# binary_watch.net
KiCad netlist of a schematic drawn in EAGLE
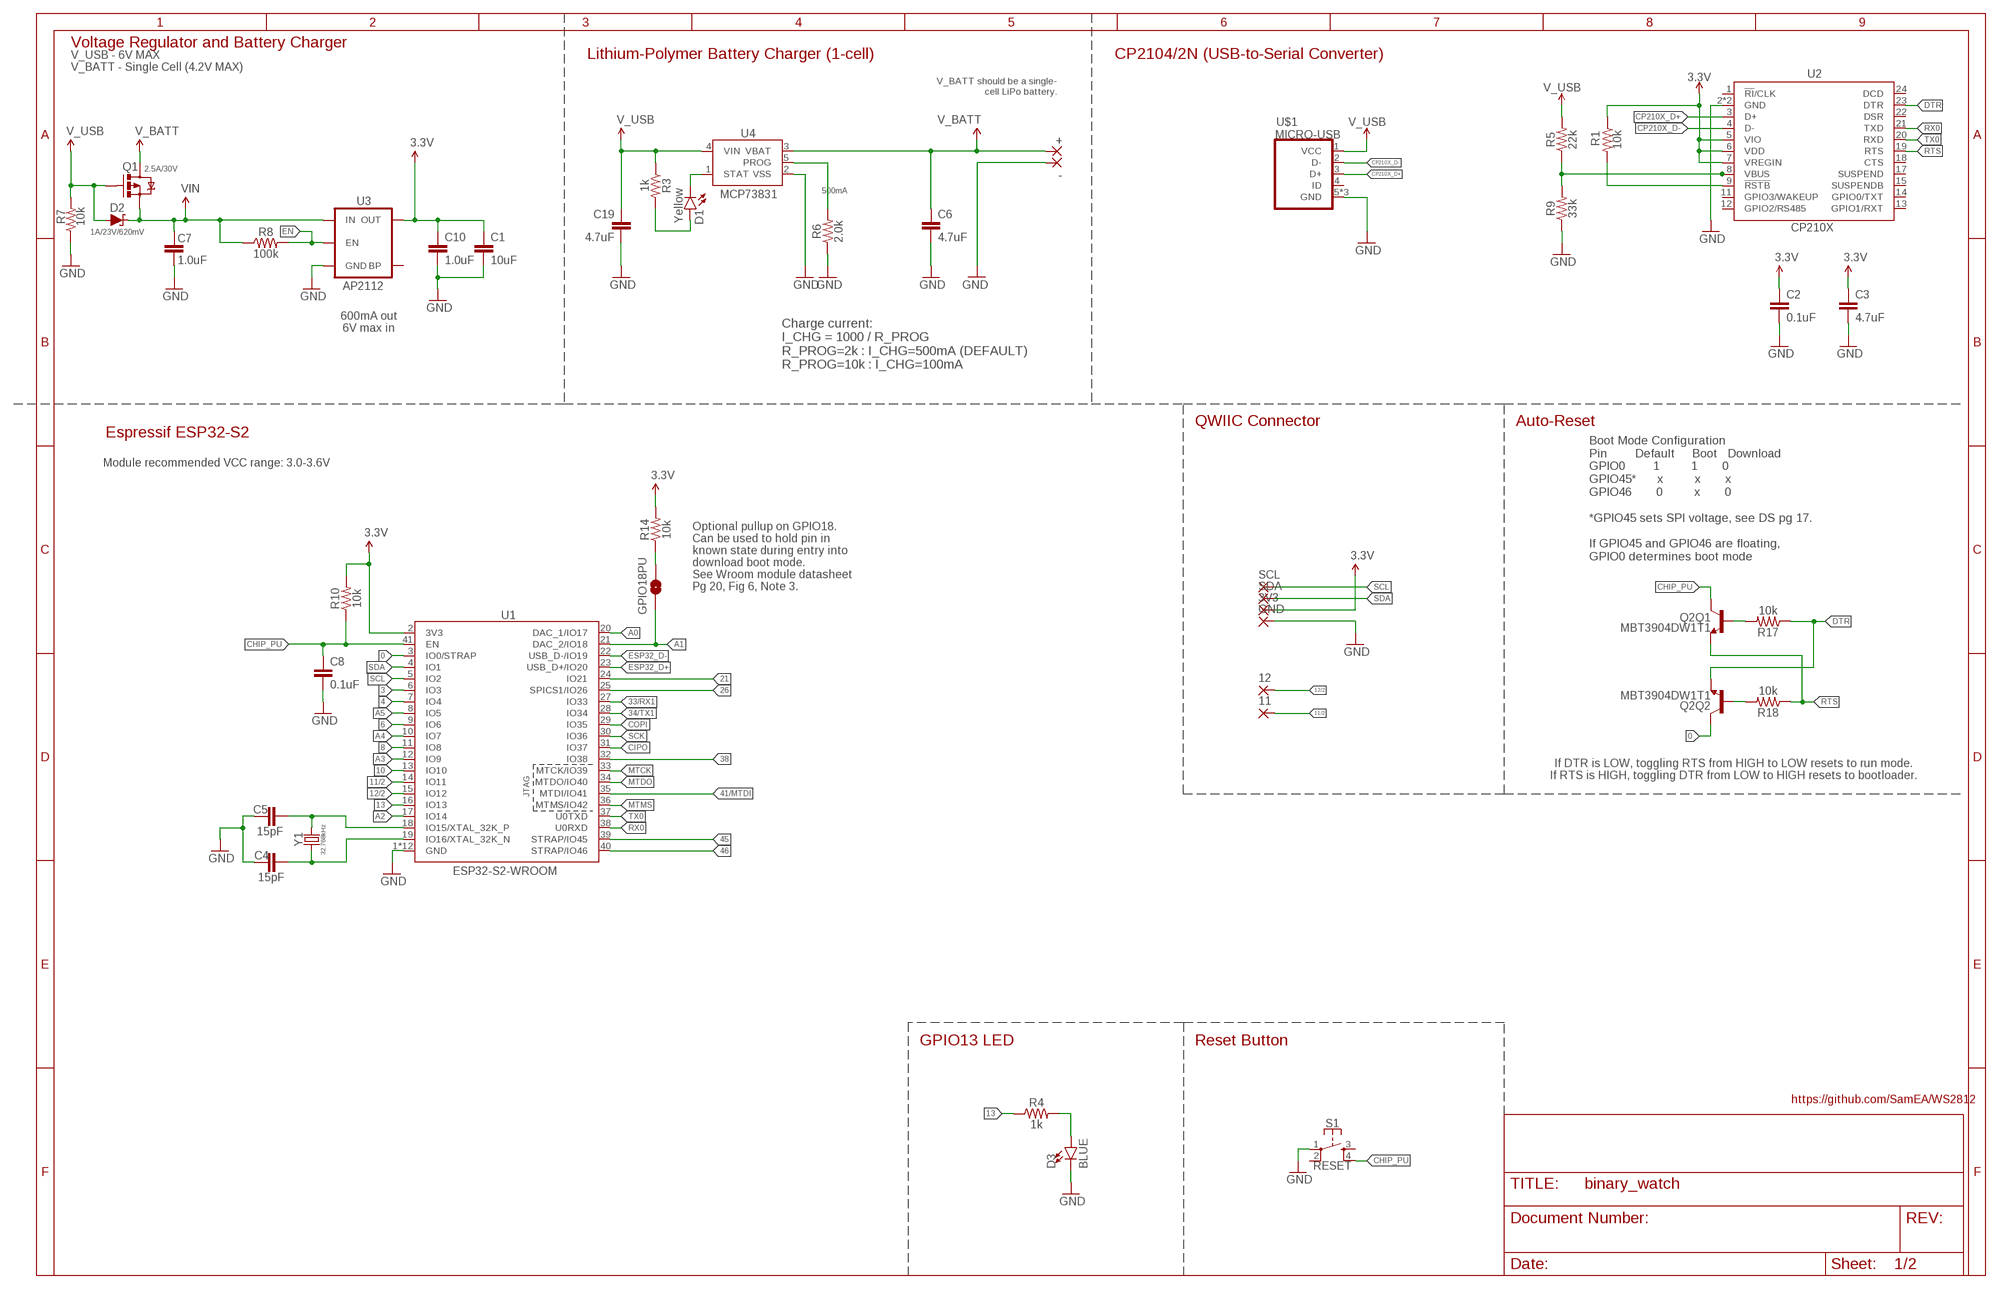
[diagram p0: schematic, sheet 1]
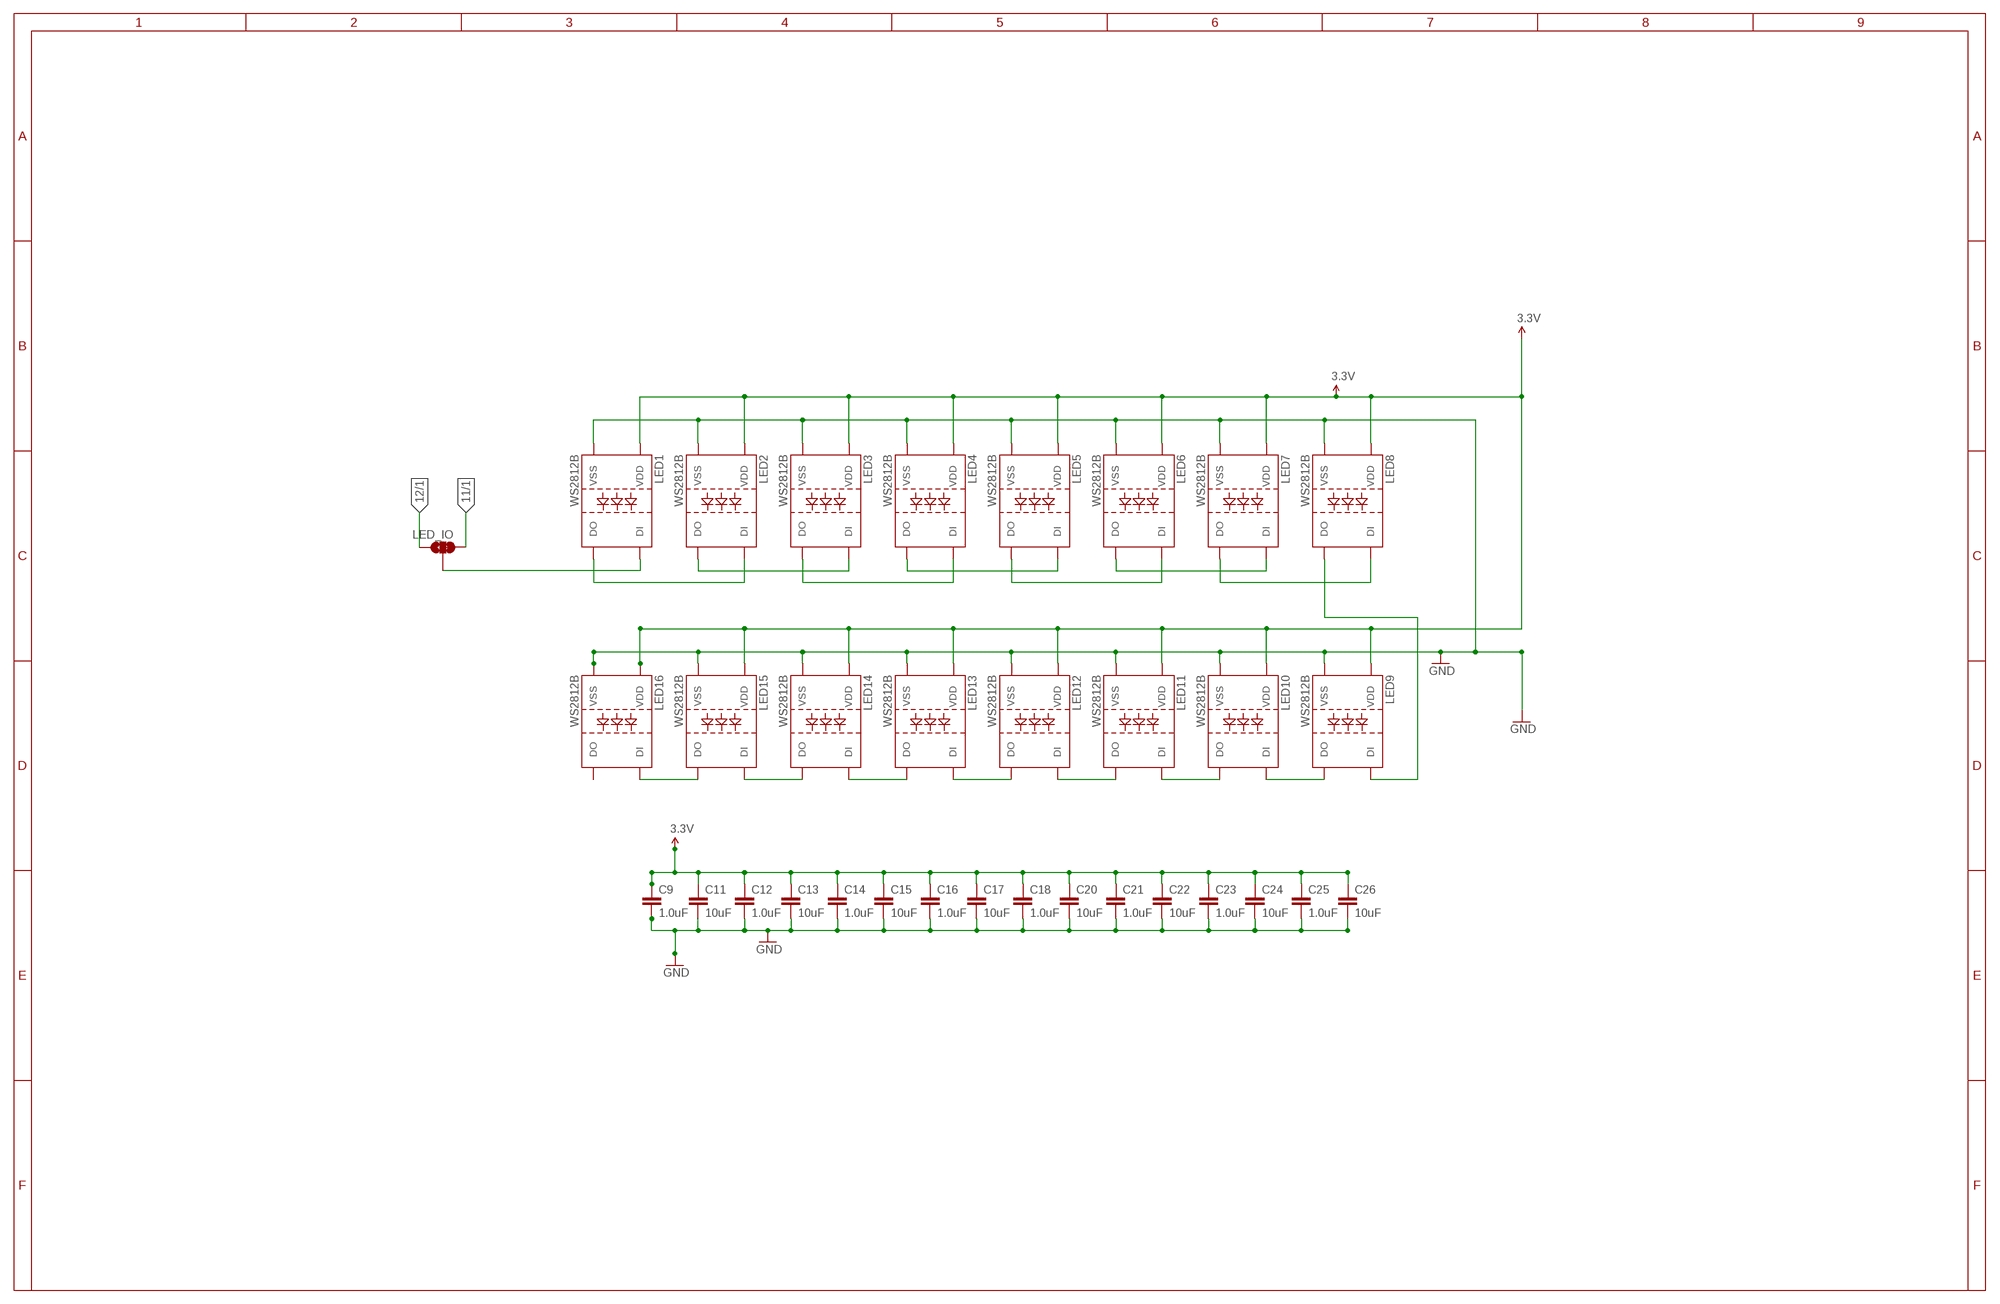
[diagram p1: schematic, sheet 2]

(export (version "E")
  (design (tool "Eeschema 10.0.6"))
  (components
    (comp (ref "C9")
      (value "1.0uF")
      (footprint "eagle-import:0402-TIGHT")
      (libsource (lib "eagle-import") (part "1.0UF-0402T-16V-10%"))
    )
    (comp (ref "C11")
      (value "10uF")
      (footprint "eagle-import:0402-TIGHT")
      (libsource (lib "eagle-import") (part "10UF-0402T-6.3V-20%"))
    )
    (comp (ref "C12")
      (value "1.0uF")
      (footprint "eagle-import:0402-TIGHT")
      (libsource (lib "eagle-import") (part "1.0UF-0402T-16V-10%"))
    )
    (comp (ref "C13")
      (value "10uF")
      (footprint "eagle-import:0402-TIGHT")
      (libsource (lib "eagle-import") (part "10UF-0402T-6.3V-20%"))
    )
    (comp (ref "C14")
      (value "1.0uF")
      (footprint "eagle-import:0402-TIGHT")
      (libsource (lib "eagle-import") (part "1.0UF-0402T-16V-10%"))
    )
    (comp (ref "C15")
      (value "10uF")
      (footprint "eagle-import:0402-TIGHT")
      (libsource (lib "eagle-import") (part "10UF-0402T-6.3V-20%"))
    )
    (comp (ref "C16")
      (value "1.0uF")
      (footprint "eagle-import:0402-TIGHT")
      (libsource (lib "eagle-import") (part "1.0UF-0402T-16V-10%"))
    )
    (comp (ref "C17")
      (value "10uF")
      (footprint "eagle-import:0402-TIGHT")
      (libsource (lib "eagle-import") (part "10UF-0402T-6.3V-20%"))
    )
    (comp (ref "C18")
      (value "1.0uF")
      (footprint "eagle-import:0402-TIGHT")
      (libsource (lib "eagle-import") (part "1.0UF-0402T-16V-10%"))
    )
    (comp (ref "C20")
      (value "10uF")
      (footprint "eagle-import:0402-TIGHT")
      (libsource (lib "eagle-import") (part "10UF-0402T-6.3V-20%"))
    )
    (comp (ref "C21")
      (value "1.0uF")
      (footprint "eagle-import:0402-TIGHT")
      (libsource (lib "eagle-import") (part "1.0UF-0402T-16V-10%"))
    )
    (comp (ref "C22")
      (value "10uF")
      (footprint "eagle-import:0402-TIGHT")
      (libsource (lib "eagle-import") (part "10UF-0402T-6.3V-20%"))
    )
    (comp (ref "C23")
      (value "1.0uF")
      (footprint "eagle-import:0402-TIGHT")
      (libsource (lib "eagle-import") (part "1.0UF-0402T-16V-10%"))
    )
    (comp (ref "C24")
      (value "10uF")
      (footprint "eagle-import:0402-TIGHT")
      (libsource (lib "eagle-import") (part "10UF-0402T-6.3V-20%"))
    )
    (comp (ref "C25")
      (value "1.0uF")
      (footprint "eagle-import:0402-TIGHT")
      (libsource (lib "eagle-import") (part "1.0UF-0402T-16V-10%"))
    )
    (comp (ref "C26")
      (value "10uF")
      (footprint "eagle-import:0402-TIGHT")
      (libsource (lib "eagle-import") (part "10UF-0402T-6.3V-20%"))
    )
    (comp (ref "LED1")
      (value "WS2812B")
      (footprint "eagle-import:WS2812B")
      (libsource (lib "eagle-import") (part "WS2812B"))
    )
    (comp (ref "LED2")
      (value "WS2812B")
      (footprint "eagle-import:WS2812B")
      (libsource (lib "eagle-import") (part "WS2812B"))
    )
    (comp (ref "LED3")
      (value "WS2812B")
      (footprint "eagle-import:WS2812B")
      (libsource (lib "eagle-import") (part "WS2812B"))
    )
    (comp (ref "LED4")
      (value "WS2812B")
      (footprint "eagle-import:WS2812B")
      (libsource (lib "eagle-import") (part "WS2812B"))
    )
    (comp (ref "LED5")
      (value "WS2812B")
      (footprint "eagle-import:WS2812B")
      (libsource (lib "eagle-import") (part "WS2812B"))
    )
    (comp (ref "LED6")
      (value "WS2812B")
      (footprint "eagle-import:WS2812B")
      (libsource (lib "eagle-import") (part "WS2812B"))
    )
    (comp (ref "LED7")
      (value "WS2812B")
      (footprint "eagle-import:WS2812B")
      (libsource (lib "eagle-import") (part "WS2812B"))
    )
    (comp (ref "LED8")
      (value "WS2812B")
      (footprint "eagle-import:WS2812B")
      (libsource (lib "eagle-import") (part "WS2812B"))
    )
    (comp (ref "LED9")
      (value "WS2812B")
      (footprint "eagle-import:WS2812B")
      (libsource (lib "eagle-import") (part "WS2812B"))
    )
    (comp (ref "LED10")
      (value "WS2812B")
      (footprint "eagle-import:WS2812B")
      (libsource (lib "eagle-import") (part "WS2812B"))
    )
    (comp (ref "LED11")
      (value "WS2812B")
      (footprint "eagle-import:WS2812B")
      (libsource (lib "eagle-import") (part "WS2812B"))
    )
    (comp (ref "LED12")
      (value "WS2812B")
      (footprint "eagle-import:WS2812B")
      (libsource (lib "eagle-import") (part "WS2812B"))
    )
    (comp (ref "LED13")
      (value "WS2812B")
      (footprint "eagle-import:WS2812B")
      (libsource (lib "eagle-import") (part "WS2812B"))
    )
    (comp (ref "LED14")
      (value "WS2812B")
      (footprint "eagle-import:WS2812B")
      (libsource (lib "eagle-import") (part "WS2812B"))
    )
    (comp (ref "LED15")
      (value "WS2812B")
      (footprint "eagle-import:WS2812B")
      (libsource (lib "eagle-import") (part "WS2812B"))
    )
    (comp (ref "LED16")
      (value "WS2812B")
      (footprint "eagle-import:WS2812B")
      (libsource (lib "eagle-import") (part "WS2812B"))
    )
    (comp (ref "LED_IO")
      (value "JUMPER-SMT_3_1-NC_TRACE_SILK")
      (footprint "eagle-import:SMT-JUMPER_3_1-NC_TRACE_SILK")
      (libsource (lib "eagle-import") (part "JUMPER-SMT_3_1-NC_TRACE_SILK"))
    )
    (comp (ref "+")
      (value "WIREPAD1,6/0,8")
      (footprint "eagle-import:1,6_0,8")
      (libsource (lib "eagle-import") (part "WIREPAD1,6/0,8"))
    )
    (comp (ref "-")
      (value "WIREPAD1,6/0,8")
      (footprint "eagle-import:1,6_0,8")
      (libsource (lib "eagle-import") (part "WIREPAD1,6/0,8"))
    )
    (comp (ref "3V3")
      (value "1,6/0,8")
      (footprint "eagle-import:1,6_0,8")
      (libsource (lib "eagle-import") (part "1,6/0,8"))
    )
    (comp (ref "11")
      (value "1,6/0,8")
      (footprint "eagle-import:1,6_0,8")
      (libsource (lib "eagle-import") (part "1,6/0,8"))
    )
    (comp (ref "12")
      (value "1,6/0,8")
      (footprint "eagle-import:1,6_0,8")
      (libsource (lib "eagle-import") (part "1,6/0,8"))
    )
    (comp (ref "C1")
      (value "10uF")
      (footprint "eagle-import:0402-TIGHT")
      (libsource (lib "eagle-import") (part "10UF-0402T-6.3V-20%"))
    )
    (comp (ref "C2")
      (value "0.1uF")
      (footprint "eagle-import:0402-TIGHT")
      (libsource (lib "eagle-import") (part "0.1UF-0402T-16V-10%"))
    )
    (comp (ref "C3")
      (value "4.7uF")
      (footprint "eagle-import:0402-TIGHT")
      (libsource (lib "eagle-import") (part "4.7UF-0402_TIGHT-6.3V-20%-X5R"))
    )
    (comp (ref "C4")
      (value "15pF")
      (footprint "eagle-import:0402-TIGHT")
      (libsource (lib "eagle-import") (part "15PF-0402T-50V-5%"))
    )
    (comp (ref "C5")
      (value "15pF")
      (footprint "eagle-import:0402-TIGHT")
      (libsource (lib "eagle-import") (part "15PF-0402T-50V-5%"))
    )
    (comp (ref "C6")
      (value "4.7uF")
      (footprint "eagle-import:0402-TIGHT")
      (libsource (lib "eagle-import") (part "4.7UF-0402_TIGHT-6.3V-20%-X5R"))
    )
    (comp (ref "C7")
      (value "1.0uF")
      (footprint "eagle-import:0402-TIGHT")
      (libsource (lib "eagle-import") (part "1.0UF-0402T-16V-10%"))
    )
    (comp (ref "C8")
      (value "0.1uF")
      (footprint "eagle-import:0402-TIGHT")
      (libsource (lib "eagle-import") (part "0.1UF-0402T-16V-10%"))
    )
    (comp (ref "C10")
      (value "1.0uF")
      (footprint "eagle-import:0402-TIGHT")
      (libsource (lib "eagle-import") (part "1.0UF-0402T-16V-10%"))
    )
    (comp (ref "C19")
      (value "4.7uF")
      (footprint "eagle-import:0402-TIGHT")
      (libsource (lib "eagle-import") (part "4.7UF-0402_TIGHT-6.3V-20%-X5R"))
    )
    (comp (ref "D1")
      (value "Yellow")
      (footprint "eagle-import:LED-0603")
      (libsource (lib "eagle-import") (part "LED-YELLOW0603"))
    )
    (comp (ref "D2")
      (value "1A/23V/620mV")
      (footprint "eagle-import:SOD-323")
      (libsource (lib "eagle-import") (part "DIODE-SCHOTTKY-BAT20J"))
    )
    (comp (ref "D3")
      (value "BLUE")
      (footprint "eagle-import:LED-0603")
      (libsource (lib "eagle-import") (part "LED-BLUE0603"))
    )
    (comp (ref "GND")
      (value "1,6/0,8")
      (footprint "eagle-import:1,6_0,8")
      (libsource (lib "eagle-import") (part "1,6/0,8"))
    )
    (comp (ref "GPIO18PU")
      (value "JUMPER-SMT_2_NO_SILK")
      (footprint "eagle-import:SMT-JUMPER_2_NO_SILK")
      (libsource (lib "eagle-import") (part "JUMPER-SMT_2_NO_SILK"))
    )
    (comp (ref "Q1")
      (value "2.5A/30V")
      (footprint "eagle-import:SOT23-3@1")
      (libsource (lib "eagle-import") (part "MOSFET-PCHANNELDMG2307L"))
    )
    (comp (ref "Q2")
      (value "MBT3904DW1T1")
      (footprint "eagle-import:SC70-6")
      (libsource (lib "eagle-import") (part "TRANS_NPN_DUAL-MBT3904DW1T1"))
    )
    (comp (ref "R1")
      (value "10k")
      (footprint "eagle-import:0402-TIGHT")
      (libsource (lib "eagle-import") (part "10KOHM-0402T-1/16W-1%"))
    )
    (comp (ref "R3")
      (value "1k")
      (footprint "eagle-import:0402-TIGHT")
      (libsource (lib "eagle-import") (part "1KOHM-0402T-1/16W-1%"))
    )
    (comp (ref "R4")
      (value "1k")
      (footprint "eagle-import:0402-TIGHT")
      (libsource (lib "eagle-import") (part "1KOHM-0402T-1/16W-1%"))
    )
    (comp (ref "R5")
      (value "22k")
      (footprint "eagle-import:0402-TIGHT")
      (libsource (lib "eagle-import") (part "22KOHM-0402_TIGHT-1/10W-1%"))
    )
    (comp (ref "R6")
      (value "2.0k")
      (footprint "eagle-import:0603")
      (libsource (lib "eagle-import") (part "2.0KOHM1/10W5%(0603)"))
    )
    (comp (ref "R7")
      (value "10k")
      (footprint "eagle-import:0402-TIGHT")
      (libsource (lib "eagle-import") (part "10KOHM-0402T-1/16W-1%"))
    )
    (comp (ref "R8")
      (value "100k")
      (footprint "eagle-import:0402-TIGHT")
      (libsource (lib "eagle-import") (part "100KOHM-0402T-1/16W-1%"))
    )
    (comp (ref "R9")
      (value "33k")
      (footprint "eagle-import:0402-TIGHT")
      (libsource (lib "eagle-import") (part "33KOHM-0402T-1/16W-1%"))
    )
    (comp (ref "R10")
      (value "10k")
      (footprint "eagle-import:0402-TIGHT")
      (libsource (lib "eagle-import") (part "10KOHM-0402T-1/16W-1%"))
    )
    (comp (ref "R14")
      (value "10k")
      (footprint "eagle-import:0402-TIGHT")
      (libsource (lib "eagle-import") (part "10KOHM-0402T-1/16W-1%"))
    )
    (comp (ref "R17")
      (value "10k")
      (footprint "eagle-import:0402-TIGHT")
      (libsource (lib "eagle-import") (part "10KOHM-0402T-1/16W-1%"))
    )
    (comp (ref "R18")
      (value "10k")
      (footprint "eagle-import:0402-TIGHT")
      (libsource (lib "eagle-import") (part "10KOHM-0402T-1/16W-1%"))
    )
    (comp (ref "S1")
      (value "RESET")
      (footprint "eagle-import:TACTILE_SWITCH_SMD_4.6X2.8MM")
      (libsource (lib "eagle-import") (part "MOMENTARY-SWITCH-SPST-2-SMD-4.6X2.8MM"))
    )
    (comp (ref "SCL")
      (value "1,6/0,8")
      (footprint "eagle-import:1,6_0,8")
      (libsource (lib "eagle-import") (part "1,6/0,8"))
    )
    (comp (ref "SDA")
      (value "1,6/0,8")
      (footprint "eagle-import:1,6_0,8")
      (libsource (lib "eagle-import") (part "1,6/0,8"))
    )
    (comp (ref "U$1")
      (value "MICRO-USB")
      (footprint "eagle-import:MICRO-USB")
      (libsource (lib "eagle-import") (part "MICRO-USB"))
    )
    (comp (ref "U1")
      (value "ESP32-S2-WROOM")
      (footprint "eagle-import:ESP32-S2-WROOM")
      (libsource (lib "eagle-import") (part "ESP32-S2-WROOM"))
    )
    (comp (ref "U2")
      (value "CP210X")
      (footprint "eagle-import:QFN24")
      (libsource (lib "eagle-import") (part "CP2102N"))
    )
    (comp (ref "U3")
      (value "AP2112")
      (footprint "eagle-import:SOT23-5")
      (libsource (lib "eagle-import") (part "V_REG_LDOSMD"))
    )
    (comp (ref "U4")
      (value "MCP73831")
      (footprint "eagle-import:SOT23-5")
      (libsource (lib "eagle-import") (part "MCP73831"))
    )
    (comp (ref "Y1")
      (value "32.768kHz")
      (footprint "eagle-import:CRYSTAL-SMD-3.2X1.5MM")
      (libsource (lib "eagle-import") (part "CRYSTAL-32.768KHZSMD-3.2X1.5"))
    )
  )
  (nets
    (net (code "1") (name "0") (class "Default")
      (node (ref "Q2") (pin "6") (pinfunction "C_6") (pintype "passive"))
      (node (ref "U1") (pin "3") (pinfunction "IO0/STRAP_3") (pintype "bidirectional"))
    )
    (net (code "2") (name "3") (class "Default")
      (node (ref "U1") (pin "6") (pinfunction "IO3_6") (pintype "bidirectional"))
    )
    (net (code "3") (name "3.3V") (class "Default")
      (node (ref "3V3") (pin "1") (pinfunction "P_1") (pintype "passive"))
      (node (ref "C1") (pin "1") (pinfunction "1_1") (pintype "passive"))
      (node (ref "C10") (pin "1") (pinfunction "1_1") (pintype "passive"))
      (node (ref "C11") (pin "1") (pinfunction "1_1") (pintype "passive"))
      (node (ref "C12") (pin "1") (pinfunction "1_1") (pintype "passive"))
      (node (ref "C13") (pin "1") (pinfunction "1_1") (pintype "passive"))
      (node (ref "C14") (pin "1") (pinfunction "1_1") (pintype "passive"))
      (node (ref "C15") (pin "1") (pinfunction "1_1") (pintype "passive"))
      (node (ref "C16") (pin "1") (pinfunction "1_1") (pintype "passive"))
      (node (ref "C17") (pin "1") (pinfunction "1_1") (pintype "passive"))
      (node (ref "C18") (pin "1") (pinfunction "1_1") (pintype "passive"))
      (node (ref "C2") (pin "1") (pinfunction "1_1") (pintype "passive"))
      (node (ref "C20") (pin "1") (pinfunction "1_1") (pintype "passive"))
      (node (ref "C21") (pin "1") (pinfunction "1_1") (pintype "passive"))
      (node (ref "C22") (pin "1") (pinfunction "1_1") (pintype "passive"))
      (node (ref "C23") (pin "1") (pinfunction "1_1") (pintype "passive"))
      (node (ref "C24") (pin "1") (pinfunction "1_1") (pintype "passive"))
      (node (ref "C25") (pin "1") (pinfunction "1_1") (pintype "passive"))
      (node (ref "C26") (pin "1") (pinfunction "1_1") (pintype "passive"))
      (node (ref "C3") (pin "1") (pinfunction "1_1") (pintype "passive"))
      (node (ref "C9") (pin "1") (pinfunction "1_1") (pintype "passive"))
      (node (ref "LED1") (pin "1") (pinfunction "VDD_1") (pintype "bidirectional"))
      (node (ref "LED10") (pin "1") (pinfunction "VDD_1") (pintype "bidirectional"))
      (node (ref "LED11") (pin "1") (pinfunction "VDD_1") (pintype "bidirectional"))
      (node (ref "LED12") (pin "1") (pinfunction "VDD_1") (pintype "bidirectional"))
      (node (ref "LED13") (pin "1") (pinfunction "VDD_1") (pintype "bidirectional"))
      (node (ref "LED14") (pin "1") (pinfunction "VDD_1") (pintype "bidirectional"))
      (node (ref "LED15") (pin "1") (pinfunction "VDD_1") (pintype "bidirectional"))
      (node (ref "LED16") (pin "1") (pinfunction "VDD_1") (pintype "bidirectional"))
      (node (ref "LED2") (pin "1") (pinfunction "VDD_1") (pintype "bidirectional"))
      (node (ref "LED3") (pin "1") (pinfunction "VDD_1") (pintype "bidirectional"))
      (node (ref "LED4") (pin "1") (pinfunction "VDD_1") (pintype "bidirectional"))
      (node (ref "LED5") (pin "1") (pinfunction "VDD_1") (pintype "bidirectional"))
      (node (ref "LED6") (pin "1") (pinfunction "VDD_1") (pintype "bidirectional"))
      (node (ref "LED7") (pin "1") (pinfunction "VDD_1") (pintype "bidirectional"))
      (node (ref "LED8") (pin "1") (pinfunction "VDD_1") (pintype "bidirectional"))
      (node (ref "LED9") (pin "1") (pinfunction "VDD_1") (pintype "bidirectional"))
      (node (ref "R1") (pin "1") (pinfunction "1_1") (pintype "passive"))
      (node (ref "R10") (pin "2") (pinfunction "2_2") (pintype "passive"))
      (node (ref "R14") (pin "2") (pinfunction "2_2") (pintype "passive"))
      (node (ref "U1") (pin "2") (pinfunction "3V3_2") (pintype "bidirectional"))
      (node (ref "U2") (pin "5") (pinfunction "VIO_5") (pintype "bidirectional"))
      (node (ref "U2") (pin "6") (pinfunction "VDD_6") (pintype "bidirectional"))
      (node (ref "U2") (pin "7") (pinfunction "VREGIN_7") (pintype "bidirectional"))
      (node (ref "U3") (pin "5") (pinfunction "OUT_5") (pintype "passive"))
    )
    (net (code "4") (name "4") (class "Default")
      (node (ref "U1") (pin "7") (pinfunction "IO4_7") (pintype "bidirectional"))
    )
    (net (code "5") (name "6") (class "Default")
      (node (ref "U1") (pin "9") (pinfunction "IO6_9") (pintype "bidirectional"))
    )
    (net (code "6") (name "8") (class "Default")
      (node (ref "U1") (pin "11") (pinfunction "IO8_11") (pintype "bidirectional"))
    )
    (net (code "7") (name "10") (class "Default")
      (node (ref "U1") (pin "13") (pinfunction "IO10_13") (pintype "bidirectional"))
    )
    (net (code "8") (name "11") (class "Default")
      (node (ref "11") (pin "1") (pinfunction "P_1") (pintype "passive"))
      (node (ref "LED_IO") (pin "3") (pinfunction "3_3") (pintype "passive"))
      (node (ref "U1") (pin "14") (pinfunction "IO11_14") (pintype "bidirectional"))
    )
    (net (code "9") (name "12") (class "Default")
      (node (ref "12") (pin "1") (pinfunction "P_1") (pintype "passive"))
      (node (ref "LED_IO") (pin "1") (pinfunction "1_1") (pintype "passive"))
      (node (ref "U1") (pin "15") (pinfunction "IO12_15") (pintype "bidirectional"))
    )
    (net (code "10") (name "13") (class "Default")
      (node (ref "R4") (pin "1") (pinfunction "1_1") (pintype "passive"))
      (node (ref "U1") (pin "16") (pinfunction "IO13_16") (pintype "bidirectional"))
    )
    (net (code "11") (name "21") (class "Default")
      (node (ref "U1") (pin "24") (pinfunction "IO21_24") (pintype "bidirectional"))
    )
    (net (code "12") (name "26") (class "Default")
      (node (ref "U1") (pin "25") (pinfunction "SPICS1/IO26_25") (pintype "bidirectional"))
    )
    (net (code "13") (name "33{slash}RX1") (class "Default")
      (node (ref "U1") (pin "27") (pinfunction "IO33_27") (pintype "bidirectional"))
    )
    (net (code "14") (name "34{slash}TX1") (class "Default")
      (node (ref "U1") (pin "28") (pinfunction "IO34_28") (pintype "bidirectional"))
    )
    (net (code "15") (name "38") (class "Default")
      (node (ref "U1") (pin "32") (pinfunction "IO38_32") (pintype "bidirectional"))
    )
    (net (code "16") (name "41{slash}MTDI") (class "Default")
      (node (ref "U1") (pin "35") (pinfunction "MTDI/IO41_35") (pintype "bidirectional"))
    )
    (net (code "17") (name "45") (class "Default")
      (node (ref "U1") (pin "39") (pinfunction "STRAP/IO45_39") (pintype "bidirectional"))
    )
    (net (code "18") (name "46") (class "Default")
      (node (ref "U1") (pin "40") (pinfunction "STRAP/IO46_40") (pintype "bidirectional"))
    )
    (net (code "19") (name "A0") (class "Default")
      (node (ref "U1") (pin "20") (pinfunction "DAC_1/IO17_20") (pintype "bidirectional"))
    )
    (net (code "20") (name "A1") (class "Default")
      (node (ref "GPIO18PU") (pin "1") (pinfunction "1_1") (pintype "passive"))
      (node (ref "U1") (pin "21") (pinfunction "DAC_2/IO18_21") (pintype "bidirectional"))
    )
    (net (code "21") (name "A2") (class "Default")
      (node (ref "U1") (pin "17") (pinfunction "IO14_17") (pintype "bidirectional"))
    )
    (net (code "22") (name "A3") (class "Default")
      (node (ref "U1") (pin "12") (pinfunction "IO9_12") (pintype "bidirectional"))
    )
    (net (code "23") (name "A4") (class "Default")
      (node (ref "U1") (pin "10") (pinfunction "IO7_10") (pintype "bidirectional"))
    )
    (net (code "24") (name "A5") (class "Default")
      (node (ref "U1") (pin "8") (pinfunction "IO5_8") (pintype "bidirectional"))
    )
    (net (code "25") (name "CHIP_PU") (class "Default")
      (node (ref "C8") (pin "1") (pinfunction "1_1") (pintype "passive"))
      (node (ref "Q2") (pin "3") (pinfunction "C_3") (pintype "passive"))
      (node (ref "R10") (pin "1") (pinfunction "1_1") (pintype "passive"))
      (node (ref "S1") (pin "4") (pinfunction "4_4") (pintype "passive"))
      (node (ref "U1") (pin "41") (pinfunction "EN_41") (pintype "bidirectional"))
    )
    (net (code "26") (name "CIPO") (class "Default")
      (node (ref "U1") (pin "31") (pinfunction "IO37_31") (pintype "bidirectional"))
    )
    (net (code "27") (name "COPI") (class "Default")
      (node (ref "U1") (pin "29") (pinfunction "IO35_29") (pintype "bidirectional"))
    )
    (net (code "28") (name "CP210X_D+") (class "Default")
      (node (ref "U$1") (pin "3") (pinfunction "D+_3") (pintype "bidirectional"))
      (node (ref "U2") (pin "3") (pinfunction "D+_3") (pintype "bidirectional"))
    )
    (net (code "29") (name "CP210X_D-") (class "Default")
      (node (ref "U$1") (pin "2") (pinfunction "D-_2") (pintype "bidirectional"))
      (node (ref "U2") (pin "4") (pinfunction "D-_4") (pintype "bidirectional"))
    )
    (net (code "30") (name "DTR") (class "Default")
      (node (ref "Q2") (pin "1") (pinfunction "E_1") (pintype "passive"))
      (node (ref "R17") (pin "1") (pinfunction "1_1") (pintype "passive"))
      (node (ref "U2") (pin "23") (pinfunction "DTR_23") (pintype "bidirectional"))
    )
    (net (code "31") (name "EN") (class "Default")
      (node (ref "R8") (pin "2") (pinfunction "2_2") (pintype "passive"))
      (node (ref "U3") (pin "3") (pinfunction "EN_3") (pintype "input"))
    )
    (net (code "32") (name "ESP32_D+") (class "Default")
      (node (ref "U1") (pin "23") (pinfunction "USB_D+/IO20_23") (pintype "bidirectional"))
    )
    (net (code "33") (name "ESP32_D-") (class "Default")
      (node (ref "U1") (pin "22") (pinfunction "USB_D-/IO19_22") (pintype "bidirectional"))
    )
    (net (code "34") (name "GND") (class "Default")
      (node (ref "-") (pin "1") (pinfunction "P_1") (pintype "passive"))
      (node (ref "C1") (pin "2") (pinfunction "2_2") (pintype "passive"))
      (node (ref "C10") (pin "2") (pinfunction "2_2") (pintype "passive"))
      (node (ref "C11") (pin "2") (pinfunction "2_2") (pintype "passive"))
      (node (ref "C12") (pin "2") (pinfunction "2_2") (pintype "passive"))
      (node (ref "C13") (pin "2") (pinfunction "2_2") (pintype "passive"))
      (node (ref "C14") (pin "2") (pinfunction "2_2") (pintype "passive"))
      (node (ref "C15") (pin "2") (pinfunction "2_2") (pintype "passive"))
      (node (ref "C16") (pin "2") (pinfunction "2_2") (pintype "passive"))
      (node (ref "C17") (pin "2") (pinfunction "2_2") (pintype "passive"))
      (node (ref "C18") (pin "2") (pinfunction "2_2") (pintype "passive"))
      (node (ref "C19") (pin "2") (pinfunction "2_2") (pintype "passive"))
      (node (ref "C2") (pin "2") (pinfunction "2_2") (pintype "passive"))
      (node (ref "C20") (pin "2") (pinfunction "2_2") (pintype "passive"))
      (node (ref "C21") (pin "2") (pinfunction "2_2") (pintype "passive"))
      (node (ref "C22") (pin "2") (pinfunction "2_2") (pintype "passive"))
      (node (ref "C23") (pin "2") (pinfunction "2_2") (pintype "passive"))
      (node (ref "C24") (pin "2") (pinfunction "2_2") (pintype "passive"))
      (node (ref "C25") (pin "2") (pinfunction "2_2") (pintype "passive"))
      (node (ref "C26") (pin "2") (pinfunction "2_2") (pintype "passive"))
      (node (ref "C3") (pin "2") (pinfunction "2_2") (pintype "passive"))
      (node (ref "C4") (pin "1") (pinfunction "1_1") (pintype "passive"))
      (node (ref "C5") (pin "1") (pinfunction "1_1") (pintype "passive"))
      (node (ref "C6") (pin "2") (pinfunction "2_2") (pintype "passive"))
      (node (ref "C7") (pin "2") (pinfunction "2_2") (pintype "passive"))
      (node (ref "C8") (pin "2") (pinfunction "2_2") (pintype "passive"))
      (node (ref "C9") (pin "2") (pinfunction "2_2") (pintype "passive"))
      (node (ref "D3") (pin "C") (pinfunction "C_C") (pintype "passive"))
      (node (ref "GND") (pin "1") (pinfunction "P_1") (pintype "passive"))
      (node (ref "LED1") (pin "3") (pinfunction "VSS_3") (pintype "bidirectional"))
      (node (ref "LED10") (pin "3") (pinfunction "VSS_3") (pintype "bidirectional"))
      (node (ref "LED11") (pin "3") (pinfunction "VSS_3") (pintype "bidirectional"))
      (node (ref "LED12") (pin "3") (pinfunction "VSS_3") (pintype "bidirectional"))
      (node (ref "LED13") (pin "3") (pinfunction "VSS_3") (pintype "bidirectional"))
      (node (ref "LED14") (pin "3") (pinfunction "VSS_3") (pintype "bidirectional"))
      (node (ref "LED15") (pin "3") (pinfunction "VSS_3") (pintype "bidirectional"))
      (node (ref "LED16") (pin "3") (pinfunction "VSS_3") (pintype "bidirectional"))
      (node (ref "LED2") (pin "3") (pinfunction "VSS_3") (pintype "bidirectional"))
      (node (ref "LED3") (pin "3") (pinfunction "VSS_3") (pintype "bidirectional"))
      (node (ref "LED4") (pin "3") (pinfunction "VSS_3") (pintype "bidirectional"))
      (node (ref "LED5") (pin "3") (pinfunction "VSS_3") (pintype "bidirectional"))
      (node (ref "LED6") (pin "3") (pinfunction "VSS_3") (pintype "bidirectional"))
      (node (ref "LED7") (pin "3") (pinfunction "VSS_3") (pintype "bidirectional"))
      (node (ref "LED8") (pin "3") (pinfunction "VSS_3") (pintype "bidirectional"))
      (node (ref "LED9") (pin "3") (pinfunction "VSS_3") (pintype "bidirectional"))
      (node (ref "R6") (pin "1") (pinfunction "1_1") (pintype "passive"))
      (node (ref "R7") (pin "1") (pinfunction "1_1") (pintype "passive"))
      (node (ref "R9") (pin "1") (pinfunction "1_1") (pintype "passive"))
      (node (ref "S1") (pin "1") (pinfunction "1_1") (pintype "passive"))
      (node (ref "U$1") (pin "5") (pinfunction "GND_5") (pintype "power_in"))
      (node (ref "U$1") (pin "GND1") (pinfunction "GND_GND1") (pintype "power_in"))
      (node (ref "U$1") (pin "GND2") (pinfunction "GND_GND2") (pintype "power_in"))
      (node (ref "U1") (pin "1") (pinfunction "GND_1") (pintype "bidirectional"))
      (node (ref "U1") (pin "26") (pinfunction "GND_26") (pintype "bidirectional"))
      (node (ref "U1") (pin "42") (pinfunction "GND_42") (pintype "bidirectional"))
      (node (ref "U1") (pin "GNDEP0") (pinfunction "GND_GNDEP0") (pintype "bidirectional"))
      (node (ref "U1") (pin "GNDEP1") (pinfunction "GND_GNDEP1") (pintype "bidirectional"))
      (node (ref "U1") (pin "GNDEP2") (pinfunction "GND_GNDEP2") (pintype "bidirectional"))
      (node (ref "U1") (pin "GNDEP3") (pinfunction "GND_GNDEP3") (pintype "bidirectional"))
      (node (ref "U1") (pin "GNDEP4") (pinfunction "GND_GNDEP4") (pintype "bidirectional"))
      (node (ref "U1") (pin "GNDEP5") (pinfunction "GND_GNDEP5") (pintype "bidirectional"))
      (node (ref "U1") (pin "GNDEP6") (pinfunction "GND_GNDEP6") (pintype "bidirectional"))
      (node (ref "U1") (pin "GNDEP7") (pinfunction "GND_GNDEP7") (pintype "bidirectional"))
      (node (ref "U1") (pin "GNDEP8") (pinfunction "GND_GNDEP8") (pintype "bidirectional"))
      (node (ref "U2") (pin "2") (pinfunction "GND_2") (pintype "bidirectional"))
      (node (ref "U2") (pin "PAD") (pinfunction "GND_PAD") (pintype "bidirectional"))
      (node (ref "U3") (pin "2") (pinfunction "GND_2") (pintype "input"))
      (node (ref "U4") (pin "2") (pinfunction "VSS_2") (pintype "power_in"))
    )
    (net (code "35") (name "MTCK") (class "Default")
      (node (ref "U1") (pin "33") (pinfunction "MTCK/IO39_33") (pintype "bidirectional"))
    )
    (net (code "36") (name "MTDO") (class "Default")
      (node (ref "U1") (pin "34") (pinfunction "MTDO/IO40_34") (pintype "bidirectional"))
    )
    (net (code "37") (name "MTMS") (class "Default")
      (node (ref "U1") (pin "36") (pinfunction "MTMS/IO42_36") (pintype "bidirectional"))
    )
    (net (code "38") (name "Net-(D1-PadA)") (class "Default")
      (node (ref "D1") (pin "A") (pinfunction "A_A") (pintype "passive"))
      (node (ref "R3") (pin "2") (pinfunction "2_2") (pintype "passive"))
    )
    (net (code "39") (name "Net-(D3-PadA)") (class "Default")
      (node (ref "D3") (pin "A") (pinfunction "A_A") (pintype "passive"))
      (node (ref "R4") (pin "2") (pinfunction "2_2") (pintype "passive"))
    )
    (net (code "40") (name "Net-(GPIO18PU-Pad2)") (class "Default")
      (node (ref "GPIO18PU") (pin "2") (pinfunction "2_2") (pintype "passive"))
      (node (ref "R14") (pin "1") (pinfunction "1_1") (pintype "passive"))
    )
    (net (code "41") (name "Net-(LED1-DI)") (class "Default")
      (node (ref "LED1") (pin "4") (pinfunction "DI_4") (pintype "bidirectional"))
      (node (ref "LED_IO") (pin "2") (pinfunction "2_2") (pintype "passive"))
    )
    (net (code "42") (name "Net-(LED1-DO)") (class "Default")
      (node (ref "LED1") (pin "2") (pinfunction "DO_2") (pintype "bidirectional"))
      (node (ref "LED2") (pin "4") (pinfunction "DI_4") (pintype "bidirectional"))
    )
    (net (code "43") (name "Net-(LED2-DO)") (class "Default")
      (node (ref "LED2") (pin "2") (pinfunction "DO_2") (pintype "bidirectional"))
      (node (ref "LED3") (pin "4") (pinfunction "DI_4") (pintype "bidirectional"))
    )
    (net (code "44") (name "Net-(LED3-DO)") (class "Default")
      (node (ref "LED3") (pin "2") (pinfunction "DO_2") (pintype "bidirectional"))
      (node (ref "LED4") (pin "4") (pinfunction "DI_4") (pintype "bidirectional"))
    )
    (net (code "45") (name "Net-(LED4-DO)") (class "Default")
      (node (ref "LED4") (pin "2") (pinfunction "DO_2") (pintype "bidirectional"))
      (node (ref "LED5") (pin "4") (pinfunction "DI_4") (pintype "bidirectional"))
    )
    (net (code "46") (name "Net-(LED5-DO)") (class "Default")
      (node (ref "LED5") (pin "2") (pinfunction "DO_2") (pintype "bidirectional"))
      (node (ref "LED6") (pin "4") (pinfunction "DI_4") (pintype "bidirectional"))
    )
    (net (code "47") (name "Net-(LED6-DO)") (class "Default")
      (node (ref "LED6") (pin "2") (pinfunction "DO_2") (pintype "bidirectional"))
      (node (ref "LED7") (pin "4") (pinfunction "DI_4") (pintype "bidirectional"))
    )
    (net (code "48") (name "Net-(LED7-DO)") (class "Default")
      (node (ref "LED7") (pin "2") (pinfunction "DO_2") (pintype "bidirectional"))
      (node (ref "LED8") (pin "4") (pinfunction "DI_4") (pintype "bidirectional"))
    )
    (net (code "49") (name "Net-(LED8-DO)") (class "Default")
      (node (ref "LED8") (pin "2") (pinfunction "DO_2") (pintype "bidirectional"))
      (node (ref "LED9") (pin "4") (pinfunction "DI_4") (pintype "bidirectional"))
    )
    (net (code "50") (name "Net-(LED10-DI)") (class "Default")
      (node (ref "LED10") (pin "4") (pinfunction "DI_4") (pintype "bidirectional"))
      (node (ref "LED9") (pin "2") (pinfunction "DO_2") (pintype "bidirectional"))
    )
    (net (code "51") (name "Net-(LED10-DO)") (class "Default")
      (node (ref "LED10") (pin "2") (pinfunction "DO_2") (pintype "bidirectional"))
      (node (ref "LED11") (pin "4") (pinfunction "DI_4") (pintype "bidirectional"))
    )
    (net (code "52") (name "Net-(LED11-DO)") (class "Default")
      (node (ref "LED11") (pin "2") (pinfunction "DO_2") (pintype "bidirectional"))
      (node (ref "LED12") (pin "4") (pinfunction "DI_4") (pintype "bidirectional"))
    )
    (net (code "53") (name "Net-(LED12-DO)") (class "Default")
      (node (ref "LED12") (pin "2") (pinfunction "DO_2") (pintype "bidirectional"))
      (node (ref "LED13") (pin "4") (pinfunction "DI_4") (pintype "bidirectional"))
    )
    (net (code "54") (name "Net-(LED13-DO)") (class "Default")
      (node (ref "LED13") (pin "2") (pinfunction "DO_2") (pintype "bidirectional"))
      (node (ref "LED14") (pin "4") (pinfunction "DI_4") (pintype "bidirectional"))
    )
    (net (code "55") (name "Net-(LED14-DO)") (class "Default")
      (node (ref "LED14") (pin "2") (pinfunction "DO_2") (pintype "bidirectional"))
      (node (ref "LED15") (pin "4") (pinfunction "DI_4") (pintype "bidirectional"))
    )
    (net (code "56") (name "Net-(LED15-DO)") (class "Default")
      (node (ref "LED15") (pin "2") (pinfunction "DO_2") (pintype "bidirectional"))
      (node (ref "LED16") (pin "4") (pinfunction "DI_4") (pintype "bidirectional"))
    )
    (net (code "57") (name "Net-(Q2A-B)") (class "Default")
      (node (ref "Q2") (pin "5") (pinfunction "B_5") (pintype "passive"))
      (node (ref "R17") (pin "2") (pinfunction "2_2") (pintype "passive"))
    )
    (net (code "58") (name "Net-(Q2B-B)") (class "Default")
      (node (ref "Q2") (pin "2") (pinfunction "B_2") (pintype "passive"))
      (node (ref "R18") (pin "2") (pinfunction "2_2") (pintype "passive"))
    )
    (net (code "59") (name "Net-(U1-IO15{slash}XTAL_32K_P)") (class "Default")
      (node (ref "C5") (pin "2") (pinfunction "2_2") (pintype "passive"))
      (node (ref "U1") (pin "18") (pinfunction "IO15/XTAL_32K_P_18") (pintype "bidirectional"))
      (node (ref "Y1") (pin "P$2") (pinfunction "2_P$2") (pintype "passive"))
    )
    (net (code "60") (name "Net-(U1-IO16{slash}XTAL_32K_N)") (class "Default")
      (node (ref "C4") (pin "2") (pinfunction "2_2") (pintype "passive"))
      (node (ref "U1") (pin "19") (pinfunction "IO16/XTAL_32K_N_19") (pintype "bidirectional"))
      (node (ref "Y1") (pin "P$1") (pinfunction "1_P$1") (pintype "passive"))
    )
    (net (code "61") (name "Net-(U2-VBUS)") (class "Default")
      (node (ref "R5") (pin "1") (pinfunction "1_1") (pintype "passive"))
      (node (ref "R9") (pin "2") (pinfunction "2_2") (pintype "passive"))
      (node (ref "U2") (pin "8") (pinfunction "VBUS_8") (pintype "bidirectional"))
    )
    (net (code "62") (name "Net-(U2-~{RSTB})") (class "Default")
      (node (ref "R1") (pin "2") (pinfunction "2_2") (pintype "passive"))
      (node (ref "U2") (pin "9") (pinfunction "~{RSTB}_9") (pintype "bidirectional"))
    )
    (net (code "63") (name "Net-(U4-PROG)") (class "Default")
      (node (ref "R6") (pin "2") (pinfunction "2_2") (pintype "passive"))
      (node (ref "U4") (pin "5") (pinfunction "PROG_5") (pintype "input"))
    )
    (net (code "64") (name "Net-(U4-STAT)") (class "Default")
      (node (ref "D1") (pin "C") (pinfunction "C_C") (pintype "passive"))
      (node (ref "U4") (pin "1") (pinfunction "STAT_1") (pintype "output"))
    )
    (net (code "65") (name "RTS") (class "Default")
      (node (ref "Q2") (pin "4") (pinfunction "E_4") (pintype "passive"))
      (node (ref "R18") (pin "1") (pinfunction "1_1") (pintype "passive"))
      (node (ref "U2") (pin "19") (pinfunction "RTS_19") (pintype "bidirectional"))
    )
    (net (code "66") (name "RX0") (class "Default")
      (node (ref "U1") (pin "38") (pinfunction "U0RXD_38") (pintype "bidirectional"))
      (node (ref "U2") (pin "21") (pinfunction "TXD_21") (pintype "bidirectional"))
    )
    (net (code "67") (name "SCK") (class "Default")
      (node (ref "U1") (pin "30") (pinfunction "IO36_30") (pintype "bidirectional"))
    )
    (net (code "68") (name "SCL") (class "Default")
      (node (ref "SCL") (pin "1") (pinfunction "P_1") (pintype "passive"))
      (node (ref "U1") (pin "5") (pinfunction "IO2_5") (pintype "bidirectional"))
    )
    (net (code "69") (name "SDA") (class "Default")
      (node (ref "SDA") (pin "1") (pinfunction "P_1") (pintype "passive"))
      (node (ref "U1") (pin "4") (pinfunction "IO1_4") (pintype "bidirectional"))
    )
    (net (code "70") (name "TX0") (class "Default")
      (node (ref "U1") (pin "37") (pinfunction "U0TXD_37") (pintype "bidirectional"))
      (node (ref "U2") (pin "20") (pinfunction "RXD_20") (pintype "bidirectional"))
    )
    (net (code "71") (name "VIN") (class "Default")
      (node (ref "C7") (pin "1") (pinfunction "1_1") (pintype "passive"))
      (node (ref "D2") (pin "C") (pinfunction "C_C") (pintype "passive"))
      (node (ref "Q1") (pin "2") (pinfunction "S_2") (pintype "passive"))
      (node (ref "R8") (pin "1") (pinfunction "1_1") (pintype "passive"))
      (node (ref "U3") (pin "1") (pinfunction "IN_1") (pintype "input"))
    )
    (net (code "72") (name "V_BATT") (class "Default")
      (node (ref "+") (pin "1") (pinfunction "P_1") (pintype "passive"))
      (node (ref "C6") (pin "1") (pinfunction "1_1") (pintype "passive"))
      (node (ref "Q1") (pin "3") (pinfunction "D_3") (pintype "passive"))
      (node (ref "U4") (pin "3") (pinfunction "VBAT_3") (pintype "power_in"))
    )
    (net (code "73") (name "V_USB") (class "Default")
      (node (ref "C19") (pin "1") (pinfunction "1_1") (pintype "passive"))
      (node (ref "D2") (pin "A") (pinfunction "A_A") (pintype "passive"))
      (node (ref "Q1") (pin "1") (pinfunction "G_1") (pintype "passive"))
      (node (ref "R3") (pin "1") (pinfunction "1_1") (pintype "passive"))
      (node (ref "R5") (pin "2") (pinfunction "2_2") (pintype "passive"))
      (node (ref "R7") (pin "2") (pinfunction "2_2") (pintype "passive"))
      (node (ref "U$1") (pin "1") (pinfunction "VCC_1") (pintype "power_in"))
      (node (ref "U4") (pin "4") (pinfunction "VIN_4") (pintype "power_in"))
    )
    (net (code "74") (name "unconnected-(LED16-DO-Pad2)") (class "Default")
      (node (ref "LED16") (pin "2") (pinfunction "DO_2") (pintype "bidirectional"))
    )
    (net (code "75") (name "unconnected-(S1-Pad2)") (class "Default")
      (node (ref "S1") (pin "2") (pinfunction "2_2") (pintype "passive"))
    )
    (net (code "76") (name "unconnected-(S1-Pad3)") (class "Default")
      (node (ref "S1") (pin "3") (pinfunction "3_3") (pintype "passive"))
    )
    (net (code "77") (name "unconnected-(U$1-ID-Pad4)") (class "Default")
      (node (ref "U$1") (pin "4") (pinfunction "ID_4") (pintype "bidirectional"))
    )
    (net (code "78") (name "unconnected-(U2-CTS-Pad18)") (class "Default")
      (node (ref "U2") (pin "18") (pinfunction "CTS_18") (pintype "bidirectional"))
    )
    (net (code "79") (name "unconnected-(U2-DCD-Pad24)") (class "Default")
      (node (ref "U2") (pin "24") (pinfunction "DCD_24") (pintype "bidirectional"))
    )
    (net (code "80") (name "unconnected-(U2-DSR-Pad22)") (class "Default")
      (node (ref "U2") (pin "22") (pinfunction "DSR_22") (pintype "bidirectional"))
    )
    (net (code "81") (name "unconnected-(U2-GPIO0{slash}TXT-Pad14)") (class "Default")
      (node (ref "U2") (pin "14") (pinfunction "GPIO0/TXT_14") (pintype "bidirectional"))
    )
    (net (code "82") (name "unconnected-(U2-GPIO1{slash}RXT-Pad13)") (class "Default")
      (node (ref "U2") (pin "13") (pinfunction "GPIO1/RXT_13") (pintype "bidirectional"))
    )
    (net (code "83") (name "unconnected-(U2-GPIO2{slash}RS485-Pad12)") (class "Default")
      (node (ref "U2") (pin "12") (pinfunction "GPIO2/RS485_12") (pintype "bidirectional"))
    )
    (net (code "84") (name "unconnected-(U2-GPIO3{slash}WAKEUP-Pad11)") (class "Default")
      (node (ref "U2") (pin "11") (pinfunction "GPIO3/WAKEUP_11") (pintype "bidirectional"))
    )
    (net (code "85") (name "unconnected-(U2-SUSPEND-Pad17)") (class "Default")
      (node (ref "U2") (pin "17") (pinfunction "SUSPEND_17") (pintype "bidirectional"))
    )
    (net (code "86") (name "unconnected-(U2-SUSPENDB-Pad15)") (class "Default")
      (node (ref "U2") (pin "15") (pinfunction "SUSPENDB_15") (pintype "bidirectional"))
    )
    (net (code "87") (name "unconnected-(U2-~{RI}{slash}CLK-Pad1)") (class "Default")
      (node (ref "U2") (pin "1") (pinfunction "~{RI}/CLK_1") (pintype "bidirectional"))
    )
    (net (code "88") (name "unconnected-(U3-BP-Pad4)") (class "Default")
      (node (ref "U3") (pin "4") (pinfunction "BP_4") (pintype "input"))
    )
  )
)
